# MPPT-BCR.net
KiCad netlist of a schematic drawn in Altium Designer
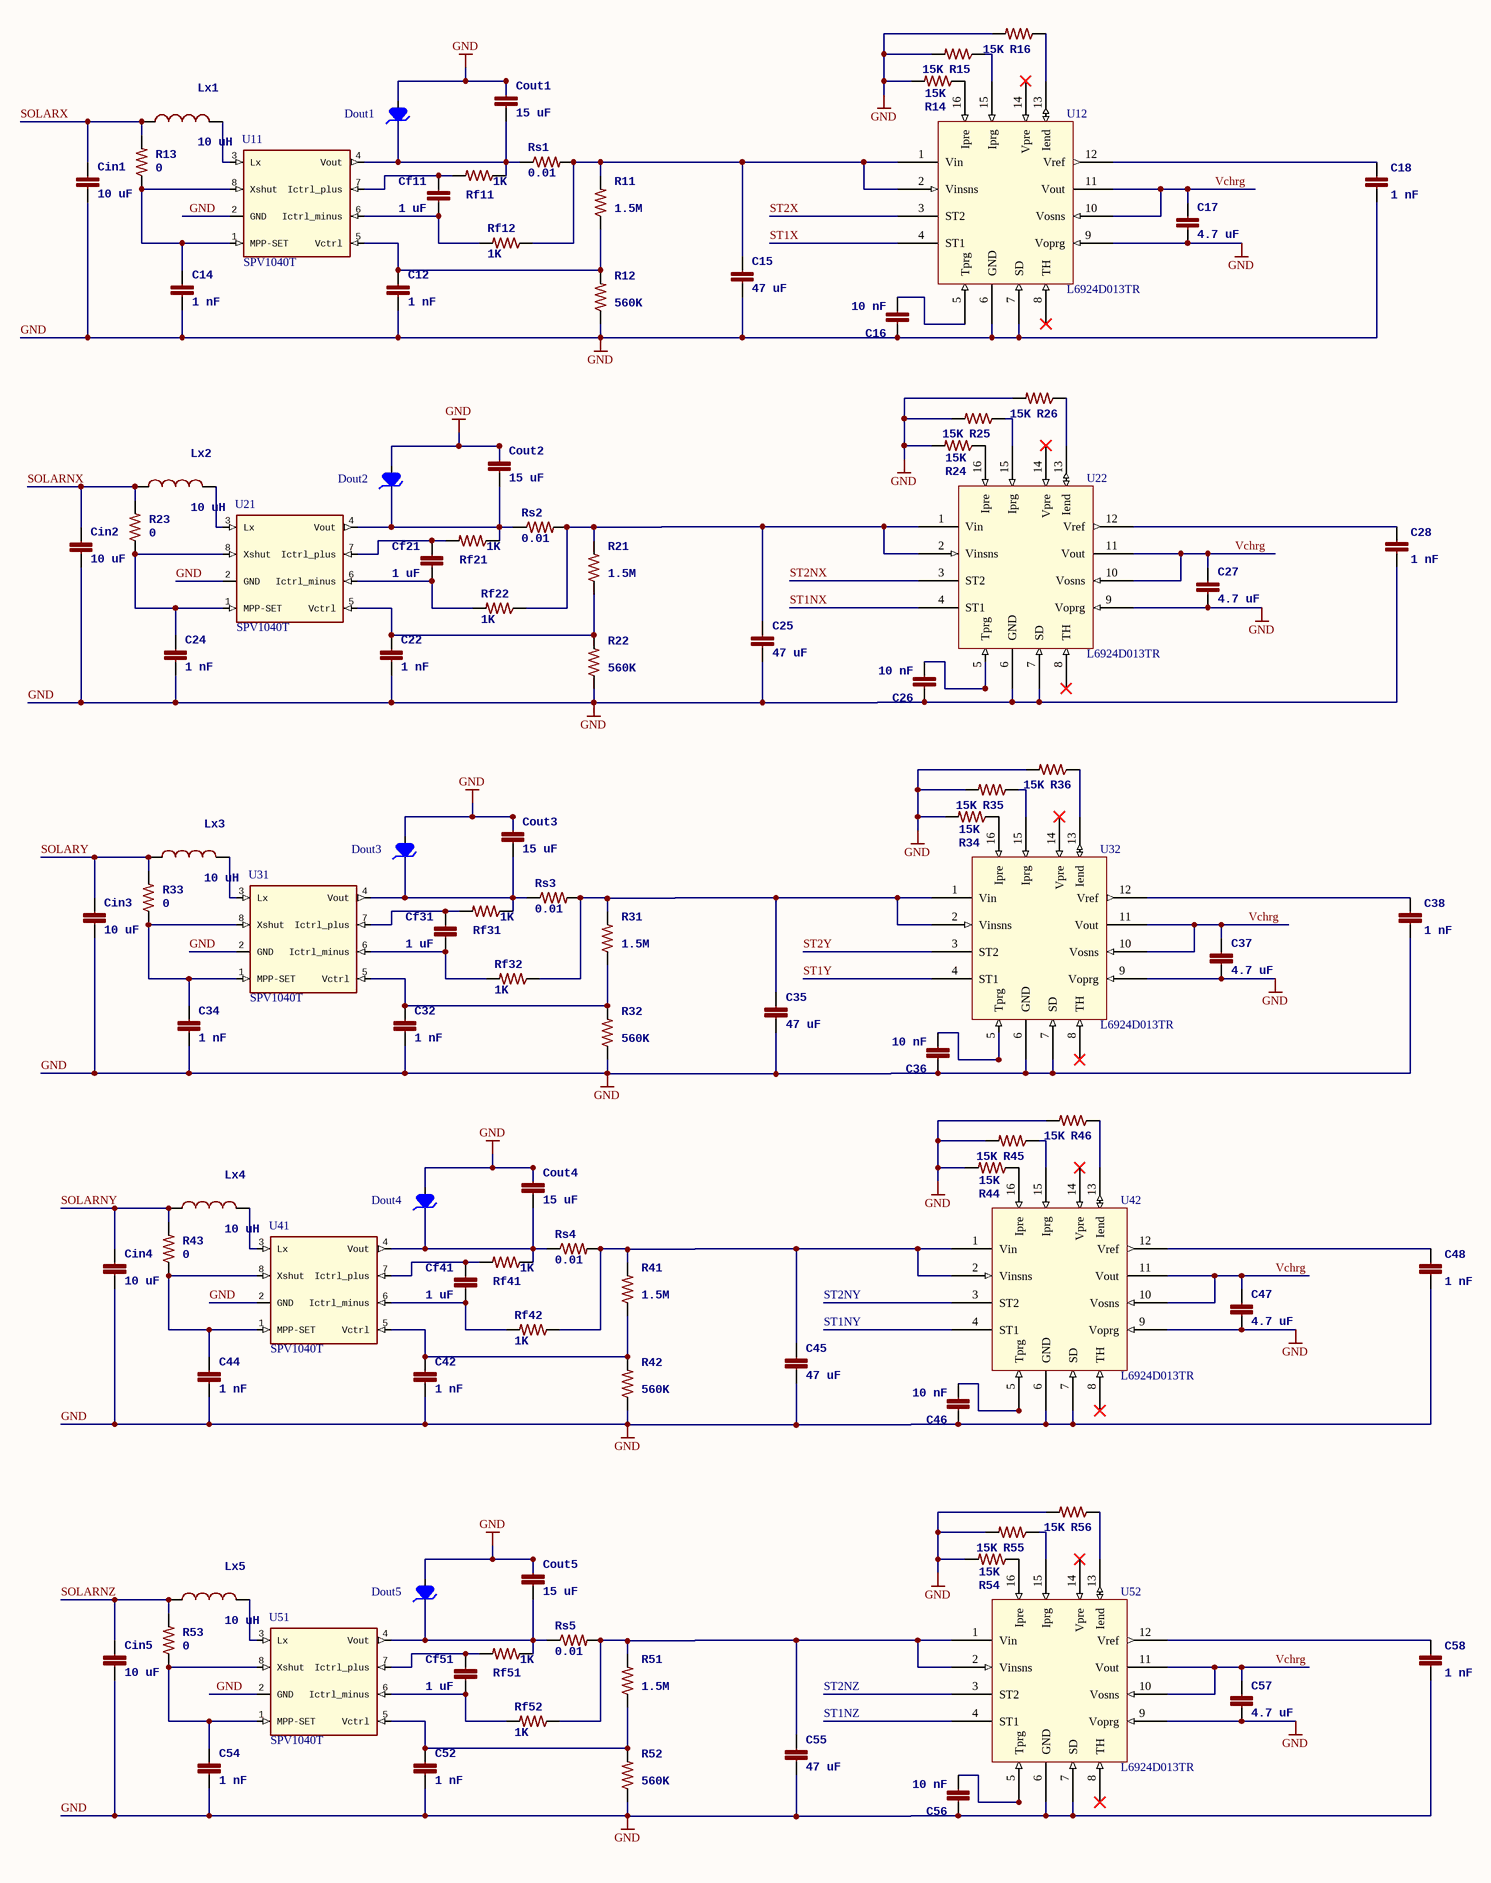
[diagram p0: MPPT-BCR.SchDoc]

(export (version "E")
  (design (tool "Eeschema 10.0.6"))
  (components
    (comp (ref "C12")
      (value "1 nF")
      (footprint "0805")
      (fields (field (name "TOLERANCE") "±10%"))
      (libsource (lib "yusend_power") (part "CAP0805_1nF"))
    )
    (comp (ref "C14")
      (value "1 nF")
      (footprint "0805")
      (fields (field (name "TOLERANCE") "±10%"))
      (libsource (lib "yusend_power") (part "CAP0805_1nF"))
    )
    (comp (ref "C15")
      (value "47 uF")
      (footprint "0805")
      (fields (field (name "TOLERANCE") "±10%"))
      (libsource (lib "yusend_power") (part "CAP0805_47000nF"))
    )
    (comp (ref "C16")
      (value "10 nF")
      (footprint "0805")
      (fields (field (name "TOLERANCE") "±10%"))
      (libsource (lib "yusend_power") (part "CAP0805_10nF"))
    )
    (comp (ref "C17")
      (value "4.7 uF")
      (footprint "0805")
      (fields (field (name "TOLERANCE") "±10%"))
      (libsource (lib "yusend_power") (part "CAP0805_4700nF"))
    )
    (comp (ref "C18")
      (value "1 nF")
      (footprint "0805")
      (fields (field (name "TOLERANCE") "±10%"))
      (libsource (lib "yusend_power") (part "CAP0805_1nF"))
    )
    (comp (ref "C22")
      (value "1 nF")
      (footprint "0805")
      (fields (field (name "TOLERANCE") "±10%"))
      (libsource (lib "yusend_power") (part "CAP0805_1nF"))
    )
    (comp (ref "C24")
      (value "1 nF")
      (footprint "0805")
      (fields (field (name "TOLERANCE") "±10%"))
      (libsource (lib "yusend_power") (part "CAP0805_1nF"))
    )
    (comp (ref "C25")
      (value "47 uF")
      (footprint "0805")
      (fields (field (name "TOLERANCE") "±10%"))
      (libsource (lib "yusend_power") (part "CAP0805_47000nF"))
    )
    (comp (ref "C26")
      (value "10 nF")
      (footprint "0805")
      (fields (field (name "TOLERANCE") "±10%"))
      (libsource (lib "yusend_power") (part "CAP0805_10nF"))
    )
    (comp (ref "C27")
      (value "4.7 uF")
      (footprint "0805")
      (fields (field (name "TOLERANCE") "±10%"))
      (libsource (lib "yusend_power") (part "CAP0805_4700nF"))
    )
    (comp (ref "C28")
      (value "1 nF")
      (footprint "0805")
      (fields (field (name "TOLERANCE") "±10%"))
      (libsource (lib "yusend_power") (part "CAP0805_1nF"))
    )
    (comp (ref "C32")
      (value "1 nF")
      (footprint "0805")
      (fields (field (name "TOLERANCE") "±10%"))
      (libsource (lib "yusend_power") (part "CAP0805_1nF"))
    )
    (comp (ref "C34")
      (value "1 nF")
      (footprint "0805")
      (fields (field (name "TOLERANCE") "±10%"))
      (libsource (lib "yusend_power") (part "CAP0805_1nF"))
    )
    (comp (ref "C35")
      (value "47 uF")
      (footprint "0805")
      (fields (field (name "TOLERANCE") "±10%"))
      (libsource (lib "yusend_power") (part "CAP0805_47000nF"))
    )
    (comp (ref "C36")
      (value "10 nF")
      (footprint "0805")
      (fields (field (name "TOLERANCE") "±10%"))
      (libsource (lib "yusend_power") (part "CAP0805_10nF"))
    )
    (comp (ref "C37")
      (value "4.7 uF")
      (footprint "0805")
      (fields (field (name "TOLERANCE") "±10%"))
      (libsource (lib "yusend_power") (part "CAP0805_4700nF"))
    )
    (comp (ref "C38")
      (value "1 nF")
      (footprint "0805")
      (fields (field (name "TOLERANCE") "±10%"))
      (libsource (lib "yusend_power") (part "CAP0805_1nF"))
    )
    (comp (ref "C42")
      (value "1 nF")
      (footprint "0805")
      (fields (field (name "TOLERANCE") "±10%"))
      (libsource (lib "yusend_power") (part "CAP0805_1nF"))
    )
    (comp (ref "C44")
      (value "1 nF")
      (footprint "0805")
      (fields (field (name "TOLERANCE") "±10%"))
      (libsource (lib "yusend_power") (part "CAP0805_1nF"))
    )
    (comp (ref "C45")
      (value "47 uF")
      (footprint "0805")
      (fields (field (name "TOLERANCE") "±10%"))
      (libsource (lib "yusend_power") (part "CAP0805_47000nF"))
    )
    (comp (ref "C46")
      (value "10 nF")
      (footprint "0805")
      (fields (field (name "TOLERANCE") "±10%"))
      (libsource (lib "yusend_power") (part "CAP0805_10nF"))
    )
    (comp (ref "C47")
      (value "4.7 uF")
      (footprint "0805")
      (fields (field (name "TOLERANCE") "±10%"))
      (libsource (lib "yusend_power") (part "CAP0805_4700nF"))
    )
    (comp (ref "C48")
      (value "1 nF")
      (footprint "0805")
      (fields (field (name "TOLERANCE") "±10%"))
      (libsource (lib "yusend_power") (part "CAP0805_1nF"))
    )
    (comp (ref "C52")
      (value "1 nF")
      (footprint "0805")
      (fields (field (name "TOLERANCE") "±10%"))
      (libsource (lib "yusend_power") (part "CAP0805_1nF"))
    )
    (comp (ref "C54")
      (value "1 nF")
      (footprint "0805")
      (fields (field (name "TOLERANCE") "±10%"))
      (libsource (lib "yusend_power") (part "CAP0805_1nF"))
    )
    (comp (ref "C55")
      (value "47 uF")
      (footprint "0805")
      (fields (field (name "TOLERANCE") "±10%"))
      (libsource (lib "yusend_power") (part "CAP0805_47000nF"))
    )
    (comp (ref "C56")
      (value "10 nF")
      (footprint "0805")
      (fields (field (name "TOLERANCE") "±10%"))
      (libsource (lib "yusend_power") (part "CAP0805_10nF"))
    )
    (comp (ref "C57")
      (value "4.7 uF")
      (footprint "0805")
      (fields (field (name "TOLERANCE") "±10%"))
      (libsource (lib "yusend_power") (part "CAP0805_4700nF"))
    )
    (comp (ref "C58")
      (value "1 nF")
      (footprint "0805")
      (fields (field (name "TOLERANCE") "±10%"))
      (libsource (lib "yusend_power") (part "CAP0805_1nF"))
    )
    (comp (ref "Cf11")
      (value "1 uF")
      (footprint "0805")
      (fields
        (field (name "MANUFACTURER") "Kemet")
        (field (name "MANUFACTURER PART NUMBER") "C0805C105K8RACTU")
        (field (name "TOLERANCE") "±10%")
      )
      (libsource (lib "yusend_power") (part "CAP0805_1uF"))
    )
    (comp (ref "Cf21")
      (value "1 uF")
      (footprint "0805")
      (fields
        (field (name "MANUFACTURER") "Kemet")
        (field (name "MANUFACTURER PART NUMBER") "C0805C105K8RACTU")
        (field (name "TOLERANCE") "±10%")
      )
      (libsource (lib "yusend_power") (part "CAP0805_1uF"))
    )
    (comp (ref "Cf31")
      (value "1 uF")
      (footprint "0805")
      (fields
        (field (name "MANUFACTURER") "Kemet")
        (field (name "MANUFACTURER PART NUMBER") "C0805C105K8RACTU")
        (field (name "TOLERANCE") "±10%")
      )
      (libsource (lib "yusend_power") (part "CAP0805_1uF"))
    )
    (comp (ref "Cf41")
      (value "1 uF")
      (footprint "0805")
      (fields
        (field (name "MANUFACTURER") "Kemet")
        (field (name "MANUFACTURER PART NUMBER") "C0805C105K8RACTU")
        (field (name "TOLERANCE") "±10%")
      )
      (libsource (lib "yusend_power") (part "CAP0805_1uF"))
    )
    (comp (ref "Cf51")
      (value "1 uF")
      (footprint "0805")
      (fields
        (field (name "MANUFACTURER") "Kemet")
        (field (name "MANUFACTURER PART NUMBER") "C0805C105K8RACTU")
        (field (name "TOLERANCE") "±10%")
      )
      (libsource (lib "yusend_power") (part "CAP0805_1uF"))
    )
    (comp (ref "Cin1")
      (value "10 uF")
      (footprint "0805")
      (fields (field (name "TOLERANCE") "±10%"))
      (libsource (lib "yusend_power") (part "CAP0805_10uF"))
    )
    (comp (ref "Cin2")
      (value "10 uF")
      (footprint "0805")
      (fields (field (name "TOLERANCE") "±10%"))
      (libsource (lib "yusend_power") (part "CAP0805_10uF"))
    )
    (comp (ref "Cin3")
      (value "10 uF")
      (footprint "0805")
      (fields (field (name "TOLERANCE") "±10%"))
      (libsource (lib "yusend_power") (part "CAP0805_10uF"))
    )
    (comp (ref "Cin4")
      (value "10 uF")
      (footprint "0805")
      (fields (field (name "TOLERANCE") "±10%"))
      (libsource (lib "yusend_power") (part "CAP0805_10uF"))
    )
    (comp (ref "Cin5")
      (value "10 uF")
      (footprint "0805")
      (fields (field (name "TOLERANCE") "±10%"))
      (libsource (lib "yusend_power") (part "CAP0805_10uF"))
    )
    (comp (ref "Cout1")
      (value "15 uF")
      (footprint "1210")
      (fields (field (name "TOLERANCE") "±10%"))
      (libsource (lib "yusend_power") (part "CAP0805_15uF"))
    )
    (comp (ref "Cout2")
      (value "15 uF")
      (footprint "1210")
      (fields (field (name "TOLERANCE") "±10%"))
      (libsource (lib "yusend_power") (part "CAP0805_15uF"))
    )
    (comp (ref "Cout3")
      (value "15 uF")
      (footprint "1210")
      (fields (field (name "TOLERANCE") "±10%"))
      (libsource (lib "yusend_power") (part "CAP0805_15uF"))
    )
    (comp (ref "Cout4")
      (value "15 uF")
      (footprint "1210")
      (fields (field (name "TOLERANCE") "±10%"))
      (libsource (lib "yusend_power") (part "CAP0805_15uF"))
    )
    (comp (ref "Cout5")
      (value "15 uF")
      (footprint "1210")
      (fields (field (name "TOLERANCE") "±10%"))
      (libsource (lib "yusend_power") (part "CAP0805_15uF"))
    )
    (comp (ref "Dout1")
      (value "Diode_Zener")
      (footprint "STmite")
      (fields (field (name "TOLERANCE") "±5%"))
      (libsource (lib "yusend_power") (part "Diode_Zener"))
    )
    (comp (ref "Dout2")
      (value "Diode_Zener")
      (footprint "STmite")
      (fields (field (name "TOLERANCE") "±5%"))
      (libsource (lib "") (part "Diode_Zener_1"))
    )
    (comp (ref "Dout3")
      (value "Diode_Zener")
      (footprint "STmite")
      (fields (field (name "TOLERANCE") "±5%"))
      (libsource (lib "yusend_power") (part "Diode_Zener"))
    )
    (comp (ref "Dout4")
      (value "Diode_Zener")
      (footprint "STmite")
      (fields (field (name "TOLERANCE") "±5%"))
      (libsource (lib "yusend_power") (part "Diode_Zener"))
    )
    (comp (ref "Dout5")
      (value "Diode_Zener")
      (footprint "STmite")
      (fields (field (name "TOLERANCE") "±5%"))
      (libsource (lib "yusend_power") (part "Diode_Zener"))
    )
    (comp (ref "Lx1")
      (value "10 uH")
      (footprint "1007")
      (libsource (lib "yusend_power") (part "INDUCTOR1007"))
    )
    (comp (ref "Lx2")
      (value "10 uH")
      (footprint "1007")
      (libsource (lib "yusend_power") (part "INDUCTOR1007"))
    )
    (comp (ref "Lx3")
      (value "10 uH")
      (footprint "1007")
      (libsource (lib "yusend_power") (part "INDUCTOR1007"))
    )
    (comp (ref "Lx4")
      (value "10 uH")
      (footprint "1007")
      (libsource (lib "yusend_power") (part "INDUCTOR1007"))
    )
    (comp (ref "Lx5")
      (value "10 uH")
      (footprint "1007")
      (libsource (lib "yusend_power") (part "INDUCTOR1007"))
    )
    (comp (ref "R11")
      (value "1.5M")
      (footprint "0805")
      (fields
        (field (name "MANUFACTURER") "TE Connectivity")
        (field (name "MANUFACTURER PART NUMBER") "1625856-2")
        (field (name "TOLERANCE") "±10%")
      )
      (libsource (lib "yusend_power") (part "RES_0805_1500K"))
    )
    (comp (ref "R12")
      (value "560K")
      (footprint "0805")
      (fields
        (field (name "MANUFACTURER") "TE Connectivity")
        (field (name "MANUFACTURER PART NUMBER") "1625856-2")
        (field (name "TOLERANCE") "±10%")
      )
      (libsource (lib "yusend_power") (part "RES_0805_560K"))
    )
    (comp (ref "R13")
      (value "0")
      (footprint "0805")
      (fields
        (field (name "MANUFACTURER") "TE Connectivity")
        (field (name "MANUFACTURER PART NUMBER") "1625856-2")
        (field (name "TOLERANCE") "±10%")
      )
      (libsource (lib "yusend_power") (part "RES_0805_0"))
    )
    (comp (ref "R14")
      (value "15K")
      (footprint "0805")
      (fields
        (field (name "MANUFACTURER") "TE Connectivity")
        (field (name "MANUFACTURER PART NUMBER") "1625856-2")
        (field (name "TOLERANCE") "±10%")
      )
      (libsource (lib "yusend_power") (part "RES_0805_15K"))
    )
    (comp (ref "R15")
      (value "15K")
      (footprint "0805")
      (fields
        (field (name "MANUFACTURER") "TE Connectivity")
        (field (name "MANUFACTURER PART NUMBER") "1625856-2")
        (field (name "TOLERANCE") "±10%")
      )
      (libsource (lib "yusend_power") (part "RES_0805_15K"))
    )
    (comp (ref "R16")
      (value "15K")
      (footprint "0805")
      (fields
        (field (name "MANUFACTURER") "TE Connectivity")
        (field (name "MANUFACTURER PART NUMBER") "1625856-2")
        (field (name "TOLERANCE") "±10%")
      )
      (libsource (lib "yusend_power") (part "RES_0805_15K"))
    )
    (comp (ref "R21")
      (value "1.5M")
      (footprint "0805")
      (fields
        (field (name "MANUFACTURER") "TE Connectivity")
        (field (name "MANUFACTURER PART NUMBER") "1625856-2")
        (field (name "TOLERANCE") "±10%")
      )
      (libsource (lib "yusend_power") (part "RES_0805_1500K"))
    )
    (comp (ref "R22")
      (value "560K")
      (footprint "0805")
      (fields
        (field (name "MANUFACTURER") "TE Connectivity")
        (field (name "MANUFACTURER PART NUMBER") "1625856-2")
        (field (name "TOLERANCE") "±10%")
      )
      (libsource (lib "yusend_power") (part "RES_0805_560K"))
    )
    (comp (ref "R23")
      (value "0")
      (footprint "0805")
      (fields
        (field (name "MANUFACTURER") "TE Connectivity")
        (field (name "MANUFACTURER PART NUMBER") "1625856-2")
        (field (name "TOLERANCE") "±10%")
      )
      (libsource (lib "yusend_power") (part "RES_0805_0"))
    )
    (comp (ref "R24")
      (value "15K")
      (footprint "0805")
      (fields
        (field (name "MANUFACTURER") "TE Connectivity")
        (field (name "MANUFACTURER PART NUMBER") "1625856-2")
        (field (name "TOLERANCE") "±10%")
      )
      (libsource (lib "yusend_power") (part "RES_0805_15K"))
    )
    (comp (ref "R25")
      (value "15K")
      (footprint "0805")
      (fields
        (field (name "MANUFACTURER") "TE Connectivity")
        (field (name "MANUFACTURER PART NUMBER") "1625856-2")
        (field (name "TOLERANCE") "±10%")
      )
      (libsource (lib "yusend_power") (part "RES_0805_15K"))
    )
    (comp (ref "R26")
      (value "15K")
      (footprint "0805")
      (fields
        (field (name "MANUFACTURER") "TE Connectivity")
        (field (name "MANUFACTURER PART NUMBER") "1625856-2")
        (field (name "TOLERANCE") "±10%")
      )
      (libsource (lib "yusend_power") (part "RES_0805_15K"))
    )
    (comp (ref "R31")
      (value "1.5M")
      (footprint "0805")
      (fields
        (field (name "MANUFACTURER") "TE Connectivity")
        (field (name "MANUFACTURER PART NUMBER") "1625856-2")
        (field (name "TOLERANCE") "±10%")
      )
      (libsource (lib "yusend_power") (part "RES_0805_1500K"))
    )
    (comp (ref "R32")
      (value "560K")
      (footprint "0805")
      (fields
        (field (name "MANUFACTURER") "TE Connectivity")
        (field (name "MANUFACTURER PART NUMBER") "1625856-2")
        (field (name "TOLERANCE") "±10%")
      )
      (libsource (lib "yusend_power") (part "RES_0805_560K"))
    )
    (comp (ref "R33")
      (value "0")
      (footprint "0805")
      (fields
        (field (name "MANUFACTURER") "TE Connectivity")
        (field (name "MANUFACTURER PART NUMBER") "1625856-2")
        (field (name "TOLERANCE") "±10%")
      )
      (libsource (lib "yusend_power") (part "RES_0805_0"))
    )
    (comp (ref "R34")
      (value "15K")
      (footprint "0805")
      (fields
        (field (name "MANUFACTURER") "TE Connectivity")
        (field (name "MANUFACTURER PART NUMBER") "1625856-2")
        (field (name "TOLERANCE") "±10%")
      )
      (libsource (lib "yusend_power") (part "RES_0805_15K"))
    )
    (comp (ref "R35")
      (value "15K")
      (footprint "0805")
      (fields
        (field (name "MANUFACTURER") "TE Connectivity")
        (field (name "MANUFACTURER PART NUMBER") "1625856-2")
        (field (name "TOLERANCE") "±10%")
      )
      (libsource (lib "yusend_power") (part "RES_0805_15K"))
    )
    (comp (ref "R36")
      (value "15K")
      (footprint "0805")
      (fields
        (field (name "MANUFACTURER") "TE Connectivity")
        (field (name "MANUFACTURER PART NUMBER") "1625856-2")
        (field (name "TOLERANCE") "±10%")
      )
      (libsource (lib "yusend_power") (part "RES_0805_15K"))
    )
    (comp (ref "R41")
      (value "1.5M")
      (footprint "0805")
      (fields
        (field (name "MANUFACTURER") "TE Connectivity")
        (field (name "MANUFACTURER PART NUMBER") "1625856-2")
        (field (name "TOLERANCE") "±10%")
      )
      (libsource (lib "yusend_power") (part "RES_0805_1500K"))
    )
    (comp (ref "R42")
      (value "560K")
      (footprint "0805")
      (fields
        (field (name "MANUFACTURER") "TE Connectivity")
        (field (name "MANUFACTURER PART NUMBER") "1625856-2")
        (field (name "TOLERANCE") "±10%")
      )
      (libsource (lib "yusend_power") (part "RES_0805_560K"))
    )
    (comp (ref "R43")
      (value "0")
      (footprint "0805")
      (fields
        (field (name "MANUFACTURER") "TE Connectivity")
        (field (name "MANUFACTURER PART NUMBER") "1625856-2")
        (field (name "TOLERANCE") "±10%")
      )
      (libsource (lib "yusend_power") (part "RES_0805_0"))
    )
    (comp (ref "R44")
      (value "15K")
      (footprint "0805")
      (fields
        (field (name "MANUFACTURER") "TE Connectivity")
        (field (name "MANUFACTURER PART NUMBER") "1625856-2")
        (field (name "TOLERANCE") "±10%")
      )
      (libsource (lib "yusend_power") (part "RES_0805_15K"))
    )
    (comp (ref "R45")
      (value "15K")
      (footprint "0805")
      (fields
        (field (name "MANUFACTURER") "TE Connectivity")
        (field (name "MANUFACTURER PART NUMBER") "1625856-2")
        (field (name "TOLERANCE") "±10%")
      )
      (libsource (lib "yusend_power") (part "RES_0805_15K"))
    )
    (comp (ref "R46")
      (value "15K")
      (footprint "0805")
      (fields
        (field (name "MANUFACTURER") "TE Connectivity")
        (field (name "MANUFACTURER PART NUMBER") "1625856-2")
        (field (name "TOLERANCE") "±10%")
      )
      (libsource (lib "yusend_power") (part "RES_0805_15K"))
    )
    (comp (ref "R51")
      (value "1.5M")
      (footprint "0805")
      (fields
        (field (name "MANUFACTURER") "TE Connectivity")
        (field (name "MANUFACTURER PART NUMBER") "1625856-2")
        (field (name "TOLERANCE") "±10%")
      )
      (libsource (lib "yusend_power") (part "RES_0805_1500K"))
    )
    (comp (ref "R52")
      (value "560K")
      (footprint "0805")
      (fields
        (field (name "MANUFACTURER") "TE Connectivity")
        (field (name "MANUFACTURER PART NUMBER") "1625856-2")
        (field (name "TOLERANCE") "±10%")
      )
      (libsource (lib "yusend_power") (part "RES_0805_560K"))
    )
    (comp (ref "R53")
      (value "0")
      (footprint "0805")
      (fields
        (field (name "MANUFACTURER") "TE Connectivity")
        (field (name "MANUFACTURER PART NUMBER") "1625856-2")
        (field (name "TOLERANCE") "±10%")
      )
      (libsource (lib "yusend_power") (part "RES_0805_0"))
    )
    (comp (ref "R54")
      (value "15K")
      (footprint "0805")
      (fields
        (field (name "MANUFACTURER") "TE Connectivity")
        (field (name "MANUFACTURER PART NUMBER") "1625856-2")
        (field (name "TOLERANCE") "±10%")
      )
      (libsource (lib "yusend_power") (part "RES_0805_15K"))
    )
    (comp (ref "R55")
      (value "15K")
      (footprint "0805")
      (fields
        (field (name "MANUFACTURER") "TE Connectivity")
        (field (name "MANUFACTURER PART NUMBER") "1625856-2")
        (field (name "TOLERANCE") "±10%")
      )
      (libsource (lib "yusend_power") (part "RES_0805_15K"))
    )
    (comp (ref "R56")
      (value "15K")
      (footprint "0805")
      (fields
        (field (name "MANUFACTURER") "TE Connectivity")
        (field (name "MANUFACTURER PART NUMBER") "1625856-2")
        (field (name "TOLERANCE") "±10%")
      )
      (libsource (lib "yusend_power") (part "RES_0805_15K"))
    )
    (comp (ref "Rf11")
      (value "1K")
      (footprint "0805")
      (fields
        (field (name "MANUFACTURER") "TE Connectivity")
        (field (name "MANUFACTURER PART NUMBER") "1625856-2")
        (field (name "TOLERANCE") "±10%")
      )
      (libsource (lib "yusend_power") (part "RES_0805_1K"))
    )
    (comp (ref "Rf12")
      (value "1K")
      (footprint "0805")
      (fields
        (field (name "MANUFACTURER") "TE Connectivity")
        (field (name "MANUFACTURER PART NUMBER") "1625856-2")
        (field (name "TOLERANCE") "±10%")
      )
      (libsource (lib "yusend_power") (part "RES_0805_1K"))
    )
    (comp (ref "Rf21")
      (value "1K")
      (footprint "0805")
      (fields
        (field (name "MANUFACTURER") "TE Connectivity")
        (field (name "MANUFACTURER PART NUMBER") "1625856-2")
        (field (name "TOLERANCE") "±10%")
      )
      (libsource (lib "yusend_power") (part "RES_0805_1K"))
    )
    (comp (ref "Rf22")
      (value "1K")
      (footprint "0805")
      (fields
        (field (name "MANUFACTURER") "TE Connectivity")
        (field (name "MANUFACTURER PART NUMBER") "1625856-2")
        (field (name "TOLERANCE") "±10%")
      )
      (libsource (lib "yusend_power") (part "RES_0805_1K"))
    )
    (comp (ref "Rf31")
      (value "1K")
      (footprint "0805")
      (fields
        (field (name "MANUFACTURER") "TE Connectivity")
        (field (name "MANUFACTURER PART NUMBER") "1625856-2")
        (field (name "TOLERANCE") "±10%")
      )
      (libsource (lib "yusend_power") (part "RES_0805_1K"))
    )
    (comp (ref "Rf32")
      (value "1K")
      (footprint "0805")
      (fields
        (field (name "MANUFACTURER") "TE Connectivity")
        (field (name "MANUFACTURER PART NUMBER") "1625856-2")
        (field (name "TOLERANCE") "±10%")
      )
      (libsource (lib "yusend_power") (part "RES_0805_1K"))
    )
    (comp (ref "Rf41")
      (value "1K")
      (footprint "0805")
      (fields
        (field (name "MANUFACTURER") "TE Connectivity")
        (field (name "MANUFACTURER PART NUMBER") "1625856-2")
        (field (name "TOLERANCE") "±10%")
      )
      (libsource (lib "yusend_power") (part "RES_0805_1K"))
    )
    (comp (ref "Rf42")
      (value "1K")
      (footprint "0805")
      (fields
        (field (name "MANUFACTURER") "TE Connectivity")
        (field (name "MANUFACTURER PART NUMBER") "1625856-2")
        (field (name "TOLERANCE") "±10%")
      )
      (libsource (lib "yusend_power") (part "RES_0805_1K"))
    )
    (comp (ref "Rf51")
      (value "1K")
      (footprint "0805")
      (fields
        (field (name "MANUFACTURER") "TE Connectivity")
        (field (name "MANUFACTURER PART NUMBER") "1625856-2")
        (field (name "TOLERANCE") "±10%")
      )
      (libsource (lib "yusend_power") (part "RES_0805_1K"))
    )
    (comp (ref "Rf52")
      (value "1K")
      (footprint "0805")
      (fields
        (field (name "MANUFACTURER") "TE Connectivity")
        (field (name "MANUFACTURER PART NUMBER") "1625856-2")
        (field (name "TOLERANCE") "±10%")
      )
      (libsource (lib "yusend_power") (part "RES_0805_1K"))
    )
    (comp (ref "Rs1")
      (value "0.01")
      (footprint "0805")
      (fields
        (field (name "MANUFACTURER") "TE Connectivity")
        (field (name "MANUFACTURER PART NUMBER") "1625856-2")
        (field (name "TOLERANCE") "±10%")
      )
      (libsource (lib "yusend_power") (part "RES_0805_01"))
    )
    (comp (ref "Rs2")
      (value "0.01")
      (footprint "0805")
      (fields
        (field (name "MANUFACTURER") "TE Connectivity")
        (field (name "MANUFACTURER PART NUMBER") "1625856-2")
        (field (name "TOLERANCE") "±10%")
      )
      (libsource (lib "yusend_power") (part "RES_0805_01"))
    )
    (comp (ref "Rs3")
      (value "0.01")
      (footprint "0805")
      (fields
        (field (name "MANUFACTURER") "TE Connectivity")
        (field (name "MANUFACTURER PART NUMBER") "1625856-2")
        (field (name "TOLERANCE") "±10%")
      )
      (libsource (lib "yusend_power") (part "RES_0805_01"))
    )
    (comp (ref "Rs4")
      (value "0.01")
      (footprint "0805")
      (fields
        (field (name "MANUFACTURER") "TE Connectivity")
        (field (name "MANUFACTURER PART NUMBER") "1625856-2")
        (field (name "TOLERANCE") "±10%")
      )
      (libsource (lib "yusend_power") (part "RES_0805_01"))
    )
    (comp (ref "Rs5")
      (value "0.01")
      (footprint "0805")
      (fields
        (field (name "MANUFACTURER") "TE Connectivity")
        (field (name "MANUFACTURER PART NUMBER") "1625856-2")
        (field (name "TOLERANCE") "±10%")
      )
      (libsource (lib "yusend_power") (part "RES_0805_01"))
    )
    (comp (ref "U11")
      (value "SPV1040")
      (footprint "TSSOP8")
      (fields
        (field (name "MANUFACTURER") "STMicroelectronics")
        (field (name "MANUFACTURER PART NUMBER") "SPV1040T")
      )
      (libsource (lib "yusend_power") (part "SPV1040"))
    )
    (comp (ref "U12")
      (value "L6924D013TR")
      (footprint "VQFN16_AP")
      (description "IC BATT CHRGR ION/POLY 16-VFQFPN")
      (fields (field (name "MANUFACTURER") "STMicroelectronics"))
      (libsource (lib "yusend_power") (part "L6924D013TR"))
    )
    (comp (ref "U21")
      (value "SPV1040")
      (footprint "TSSOP8")
      (fields
        (field (name "MANUFACTURER") "STMicroelectronics")
        (field (name "MANUFACTURER PART NUMBER") "SPV1040T")
      )
      (libsource (lib "") (part "SPV1040_1"))
    )
    (comp (ref "U22")
      (value "L6924D013TR")
      (footprint "VQFN16_AP")
      (description "IC BATT CHRGR ION/POLY 16-VFQFPN")
      (fields (field (name "MANUFACTURER") "STMicroelectronics"))
      (libsource (lib "yusend_power") (part "L6924D013TR"))
    )
    (comp (ref "U31")
      (value "SPV1040")
      (footprint "TSSOP8")
      (fields
        (field (name "MANUFACTURER") "STMicroelectronics")
        (field (name "MANUFACTURER PART NUMBER") "SPV1040T")
      )
      (libsource (lib "yusend_power") (part "SPV1040"))
    )
    (comp (ref "U32")
      (value "L6924D013TR")
      (footprint "VQFN16_AP")
      (description "IC BATT CHRGR ION/POLY 16-VFQFPN")
      (fields (field (name "MANUFACTURER") "STMicroelectronics"))
      (libsource (lib "yusend_power") (part "L6924D013TR"))
    )
    (comp (ref "U41")
      (value "SPV1040")
      (footprint "TSSOP8")
      (fields
        (field (name "MANUFACTURER") "STMicroelectronics")
        (field (name "MANUFACTURER PART NUMBER") "SPV1040T")
      )
      (libsource (lib "yusend_power") (part "SPV1040"))
    )
    (comp (ref "U42")
      (value "L6924D013TR")
      (footprint "VQFN16_AP")
      (description "IC BATT CHRGR ION/POLY 16-VFQFPN")
      (fields (field (name "MANUFACTURER") "STMicroelectronics"))
      (libsource (lib "yusend_power") (part "L6924D013TR"))
    )
    (comp (ref "U51")
      (value "SPV1040")
      (footprint "TSSOP8")
      (fields
        (field (name "MANUFACTURER") "STMicroelectronics")
        (field (name "MANUFACTURER PART NUMBER") "SPV1040T")
      )
      (libsource (lib "yusend_power") (part "SPV1040"))
    )
    (comp (ref "U52")
      (value "L6924D013TR")
      (footprint "VQFN16_AP")
      (description "IC BATT CHRGR ION/POLY 16-VFQFPN")
      (fields (field (name "MANUFACTURER") "STMicroelectronics"))
      (libsource (lib "yusend_power") (part "L6924D013TR"))
    )
  )
  (nets
    (net (code "1") (name "/SOLARNX") (class "Default")
      (node (ref "Cin2") (pin "1") (pinfunction "1_1") (pintype "passive"))
      (node (ref "Lx2") (pin "1") (pinfunction "1_1") (pintype "passive"))
      (node (ref "R23") (pin "2") (pinfunction "2_2") (pintype "passive"))
    )
    (net (code "2") (name "/SOLARNY") (class "Default")
      (node (ref "Cin4") (pin "1") (pinfunction "1_1") (pintype "passive"))
      (node (ref "Lx4") (pin "1") (pinfunction "1_1") (pintype "passive"))
      (node (ref "R43") (pin "2") (pinfunction "2_2") (pintype "passive"))
    )
    (net (code "3") (name "/SOLARNZ") (class "Default")
      (node (ref "Cin5") (pin "1") (pinfunction "1_1") (pintype "passive"))
      (node (ref "Lx5") (pin "1") (pinfunction "1_1") (pintype "passive"))
      (node (ref "R53") (pin "2") (pinfunction "2_2") (pintype "passive"))
    )
    (net (code "4") (name "/SOLARX") (class "Default")
      (node (ref "Cin1") (pin "1") (pinfunction "1_1") (pintype "passive"))
      (node (ref "Lx1") (pin "1") (pinfunction "1_1") (pintype "passive"))
      (node (ref "R13") (pin "2") (pinfunction "2_2") (pintype "passive"))
    )
    (net (code "5") (name "/SOLARY") (class "Default")
      (node (ref "Cin3") (pin "1") (pinfunction "1_1") (pintype "passive"))
      (node (ref "Lx3") (pin "1") (pinfunction "1_1") (pintype "passive"))
      (node (ref "R33") (pin "2") (pinfunction "2_2") (pintype "passive"))
    )
    (net (code "6") (name "/ST1NX") (class "Default")
      (node (ref "U22") (pin "4") (pinfunction "ST1_4") (pintype "open_collector"))
    )
    (net (code "7") (name "/ST1X") (class "Default")
      (node (ref "U12") (pin "4") (pinfunction "ST1_4") (pintype "open_collector"))
    )
    (net (code "8") (name "/ST1Y") (class "Default")
      (node (ref "U32") (pin "4") (pinfunction "ST1_4") (pintype "open_collector"))
    )
    (net (code "9") (name "/ST2NX") (class "Default")
      (node (ref "U22") (pin "3") (pinfunction "ST2_3") (pintype "open_collector"))
    )
    (net (code "10") (name "/ST2X") (class "Default")
      (node (ref "U12") (pin "3") (pinfunction "ST2_3") (pintype "open_collector"))
    )
    (net (code "11") (name "/ST2Y") (class "Default")
      (node (ref "U32") (pin "3") (pinfunction "ST2_3") (pintype "open_collector"))
    )
    (net (code "12") (name "/Vchrg") (class "Default")
      (node (ref "C17") (pin "1") (pinfunction "1_1") (pintype "passive"))
      (node (ref "C27") (pin "1") (pinfunction "1_1") (pintype "passive"))
      (node (ref "C37") (pin "1") (pinfunction "1_1") (pintype "passive"))
      (node (ref "C47") (pin "1") (pinfunction "1_1") (pintype "passive"))
      (node (ref "C57") (pin "1") (pinfunction "1_1") (pintype "passive"))
      (node (ref "U12") (pin "10") (pinfunction "Vosns_10") (pintype "input"))
      (node (ref "U12") (pin "11") (pinfunction "Vout_11") (pintype "power_in"))
      (node (ref "U22") (pin "10") (pinfunction "Vosns_10") (pintype "input"))
      (node (ref "U22") (pin "11") (pinfunction "Vout_11") (pintype "power_in"))
      (node (ref "U32") (pin "10") (pinfunction "Vosns_10") (pintype "input"))
      (node (ref "U32") (pin "11") (pinfunction "Vout_11") (pintype "power_in"))
      (node (ref "U42") (pin "10") (pinfunction "Vosns_10") (pintype "input"))
      (node (ref "U42") (pin "11") (pinfunction "Vout_11") (pintype "power_in"))
      (node (ref "U52") (pin "10") (pinfunction "Vosns_10") (pintype "input"))
      (node (ref "U52") (pin "11") (pinfunction "Vout_11") (pintype "power_in"))
    )
    (net (code "13") (name "GND") (class "Default")
      (node (ref "C12") (pin "2") (pinfunction "2_2") (pintype "passive"))
      (node (ref "C14") (pin "2") (pinfunction "2_2") (pintype "passive"))
      (node (ref "C15") (pin "2") (pinfunction "2_2") (pintype "passive"))
      (node (ref "C16") (pin "1") (pinfunction "1_1") (pintype "passive"))
      (node (ref "C17") (pin "2") (pinfunction "2_2") (pintype "passive"))
      (node (ref "C18") (pin "2") (pinfunction "2_2") (pintype "passive"))
      (node (ref "C22") (pin "2") (pinfunction "2_2") (pintype "passive"))
      (node (ref "C24") (pin "2") (pinfunction "2_2") (pintype "passive"))
      (node (ref "C25") (pin "2") (pinfunction "2_2") (pintype "passive"))
      (node (ref "C26") (pin "1") (pinfunction "1_1") (pintype "passive"))
      (node (ref "C27") (pin "2") (pinfunction "2_2") (pintype "passive"))
      (node (ref "C28") (pin "2") (pinfunction "2_2") (pintype "passive"))
      (node (ref "C32") (pin "2") (pinfunction "2_2") (pintype "passive"))
      (node (ref "C34") (pin "2") (pinfunction "2_2") (pintype "passive"))
      (node (ref "C35") (pin "2") (pinfunction "2_2") (pintype "passive"))
      (node (ref "C36") (pin "1") (pinfunction "1_1") (pintype "passive"))
      (node (ref "C37") (pin "2") (pinfunction "2_2") (pintype "passive"))
      (node (ref "C38") (pin "2") (pinfunction "2_2") (pintype "passive"))
      (node (ref "C42") (pin "2") (pinfunction "2_2") (pintype "passive"))
      (node (ref "C44") (pin "2") (pinfunction "2_2") (pintype "passive"))
      (node (ref "C45") (pin "2") (pinfunction "2_2") (pintype "passive"))
      (node (ref "C46") (pin "1") (pinfunction "1_1") (pintype "passive"))
      (node (ref "C47") (pin "2") (pinfunction "2_2") (pintype "passive"))
      (node (ref "C48") (pin "2") (pinfunction "2_2") (pintype "passive"))
      (node (ref "C52") (pin "2") (pinfunction "2_2") (pintype "passive"))
      (node (ref "C54") (pin "2") (pinfunction "2_2") (pintype "passive"))
      (node (ref "C55") (pin "2") (pinfunction "2_2") (pintype "passive"))
      (node (ref "C56") (pin "1") (pinfunction "1_1") (pintype "passive"))
      (node (ref "C57") (pin "2") (pinfunction "2_2") (pintype "passive"))
      (node (ref "C58") (pin "2") (pinfunction "2_2") (pintype "passive"))
      (node (ref "Cin1") (pin "2") (pinfunction "2_2") (pintype "passive"))
      (node (ref "Cin2") (pin "2") (pinfunction "2_2") (pintype "passive"))
      (node (ref "Cin3") (pin "2") (pinfunction "2_2") (pintype "passive"))
      (node (ref "Cin4") (pin "2") (pinfunction "2_2") (pintype "passive"))
      (node (ref "Cin5") (pin "2") (pinfunction "2_2") (pintype "passive"))
      (node (ref "Cout1") (pin "1") (pinfunction "1_1") (pintype "passive"))
      (node (ref "Cout2") (pin "1") (pinfunction "1_1") (pintype "passive"))
      (node (ref "Cout3") (pin "1") (pinfunction "1_1") (pintype "passive"))
      (node (ref "Cout4") (pin "1") (pinfunction "1_1") (pintype "passive"))
      (node (ref "Cout5") (pin "1") (pinfunction "1_1") (pintype "passive"))
      (node (ref "Dout1") (pin "2") (pinfunction "2_2") (pintype "passive"))
      (node (ref "Dout2") (pin "2") (pinfunction "2_2") (pintype "passive"))
      (node (ref "Dout3") (pin "2") (pinfunction "2_2") (pintype "passive"))
      (node (ref "Dout4") (pin "2") (pinfunction "2_2") (pintype "passive"))
      (node (ref "Dout5") (pin "2") (pinfunction "2_2") (pintype "passive"))
      (node (ref "R12") (pin "1") (pinfunction "1_1") (pintype "passive"))
      (node (ref "R14") (pin "2") (pinfunction "2_2") (pintype "passive"))
      (node (ref "R15") (pin "2") (pinfunction "2_2") (pintype "passive"))
      (node (ref "R16") (pin "2") (pinfunction "2_2") (pintype "passive"))
      (node (ref "R22") (pin "1") (pinfunction "1_1") (pintype "passive"))
      (node (ref "R24") (pin "2") (pinfunction "2_2") (pintype "passive"))
      (node (ref "R25") (pin "2") (pinfunction "2_2") (pintype "passive"))
      (node (ref "R26") (pin "2") (pinfunction "2_2") (pintype "passive"))
      (node (ref "R32") (pin "1") (pinfunction "1_1") (pintype "passive"))
      (node (ref "R34") (pin "2") (pinfunction "2_2") (pintype "passive"))
      (node (ref "R35") (pin "2") (pinfunction "2_2") (pintype "passive"))
      (node (ref "R36") (pin "2") (pinfunction "2_2") (pintype "passive"))
      (node (ref "R42") (pin "1") (pinfunction "1_1") (pintype "passive"))
      (node (ref "R44") (pin "2") (pinfunction "2_2") (pintype "passive"))
      (node (ref "R45") (pin "2") (pinfunction "2_2") (pintype "passive"))
      (node (ref "R46") (pin "2") (pinfunction "2_2") (pintype "passive"))
      (node (ref "R52") (pin "1") (pinfunction "1_1") (pintype "passive"))
      (node (ref "R54") (pin "2") (pinfunction "2_2") (pintype "passive"))
      (node (ref "R55") (pin "2") (pinfunction "2_2") (pintype "passive"))
      (node (ref "R56") (pin "2") (pinfunction "2_2") (pintype "passive"))
      (node (ref "U11") (pin "2") (pinfunction "GND_2") (pintype "passive"))
      (node (ref "U12") (pin "6") (pinfunction "GND_6") (pintype "power_in"))
      (node (ref "U12") (pin "7") (pinfunction "SD_7") (pintype "input"))
      (node (ref "U12") (pin "9") (pinfunction "Voprg_9") (pintype "input"))
      (node (ref "U21") (pin "2") (pinfunction "GND_2") (pintype "passive"))
      (node (ref "U22") (pin "6") (pinfunction "GND_6") (pintype "power_in"))
      (node (ref "U22") (pin "7") (pinfunction "SD_7") (pintype "input"))
      (node (ref "U22") (pin "9") (pinfunction "Voprg_9") (pintype "input"))
      (node (ref "U31") (pin "2") (pinfunction "GND_2") (pintype "passive"))
      (node (ref "U32") (pin "6") (pinfunction "GND_6") (pintype "power_in"))
      (node (ref "U32") (pin "7") (pinfunction "SD_7") (pintype "input"))
      (node (ref "U32") (pin "9") (pinfunction "Voprg_9") (pintype "input"))
      (node (ref "U41") (pin "2") (pinfunction "GND_2") (pintype "passive"))
      (node (ref "U42") (pin "6") (pinfunction "GND_6") (pintype "power_in"))
      (node (ref "U42") (pin "7") (pinfunction "SD_7") (pintype "input"))
      (node (ref "U42") (pin "9") (pinfunction "Voprg_9") (pintype "input"))
      (node (ref "U51") (pin "2") (pinfunction "GND_2") (pintype "passive"))
      (node (ref "U52") (pin "6") (pinfunction "GND_6") (pintype "power_in"))
      (node (ref "U52") (pin "7") (pinfunction "SD_7") (pintype "input"))
      (node (ref "U52") (pin "9") (pinfunction "Voprg_9") (pintype "input"))
    )
    (net (code "14") (name "Net-(U11-Ictrl_minus)") (class "Default")
      (node (ref "Cf11") (pin "2") (pinfunction "2_2") (pintype "passive"))
      (node (ref "Rf12") (pin "2") (pinfunction "2_2") (pintype "passive"))
      (node (ref "U11") (pin "6") (pinfunction "Ictrl_minus_6") (pintype "input"))
    )
    (net (code "15") (name "Net-(U11-Ictrl_plus)") (class "Default")
      (node (ref "Cf11") (pin "1") (pinfunction "1_1") (pintype "passive"))
      (node (ref "Rf11") (pin "2") (pinfunction "2_2") (pintype "passive"))
      (node (ref "U11") (pin "7") (pinfunction "Ictrl_plus_7") (pintype "input"))
    )
    (net (code "16") (name "Net-(U11-Lx)") (class "Default")
      (node (ref "Lx1") (pin "2") (pinfunction "2_2") (pintype "passive"))
      (node (ref "U11") (pin "3") (pinfunction "Lx_3") (pintype "input"))
    )
    (net (code "17") (name "Net-(U11-MPP-SET)") (class "Default")
      (node (ref "C14") (pin "1") (pinfunction "1_1") (pintype "passive"))
      (node (ref "R13") (pin "1") (pinfunction "1_1") (pintype "passive"))
      (node (ref "U11") (pin "1") (pinfunction "MPP-SET_1") (pintype "input"))
      (node (ref "U11") (pin "8") (pinfunction "Xshut_8") (pintype "input"))
    )
    (net (code "18") (name "Net-(U11-Vctrl)") (class "Default")
      (node (ref "C12") (pin "1") (pinfunction "1_1") (pintype "passive"))
      (node (ref "R11") (pin "1") (pinfunction "1_1") (pintype "passive"))
      (node (ref "R12") (pin "2") (pinfunction "2_2") (pintype "passive"))
      (node (ref "U11") (pin "5") (pinfunction "Vctrl_5") (pintype "input"))
    )
    (net (code "19") (name "Net-(U11-Vout)") (class "Default")
      (node (ref "Cout1") (pin "2") (pinfunction "2_2") (pintype "passive"))
      (node (ref "Dout1") (pin "1") (pinfunction "1_1") (pintype "passive"))
      (node (ref "Rf11") (pin "1") (pinfunction "1_1") (pintype "passive"))
      (node (ref "Rs1") (pin "1") (pinfunction "1_1") (pintype "passive"))
      (node (ref "U11") (pin "4") (pinfunction "Vout_4") (pintype "output"))
    )
    (net (code "20") (name "Net-(U12-Iend)") (class "Default")
      (node (ref "R16") (pin "1") (pinfunction "1_1") (pintype "passive"))
      (node (ref "U12") (pin "13") (pinfunction "Iend_13") (pintype "bidirectional"))
    )
    (net (code "21") (name "Net-(U12-Ipre)") (class "Default")
      (node (ref "R14") (pin "1") (pinfunction "1_1") (pintype "passive"))
      (node (ref "U12") (pin "16") (pinfunction "Ipre_16") (pintype "input"))
    )
    (net (code "22") (name "Net-(U12-Iprg)") (class "Default")
      (node (ref "R15") (pin "1") (pinfunction "1_1") (pintype "passive"))
      (node (ref "U12") (pin "15") (pinfunction "Iprg_15") (pintype "input"))
    )
    (net (code "23") (name "Net-(U12-Tprg)") (class "Default")
      (node (ref "C16") (pin "2") (pinfunction "2_2") (pintype "passive"))
      (node (ref "U12") (pin "5") (pinfunction "Tprg_5") (pintype "input"))
    )
    (net (code "24") (name "Net-(U12-Vin)") (class "Default")
      (node (ref "C15") (pin "1") (pinfunction "1_1") (pintype "passive"))
      (node (ref "R11") (pin "2") (pinfunction "2_2") (pintype "passive"))
      (node (ref "Rf12") (pin "1") (pinfunction "1_1") (pintype "passive"))
      (node (ref "Rs1") (pin "2") (pinfunction "2_2") (pintype "passive"))
      (node (ref "U12") (pin "1") (pinfunction "Vin_1") (pintype "power_in"))
      (node (ref "U12") (pin "2") (pinfunction "Vinsns_2") (pintype "input"))
    )
    (net (code "25") (name "Net-(U12-Vref)") (class "Default")
      (node (ref "C18") (pin "1") (pinfunction "1_1") (pintype "passive"))
      (node (ref "U12") (pin "12") (pinfunction "Vref_12") (pintype "output"))
    )
    (net (code "26") (name "Net-(U21-Ictrl_minus)") (class "Default")
      (node (ref "Cf21") (pin "2") (pinfunction "2_2") (pintype "passive"))
      (node (ref "Rf22") (pin "2") (pinfunction "2_2") (pintype "passive"))
      (node (ref "U21") (pin "6") (pinfunction "Ictrl_minus_6") (pintype "input"))
    )
    (net (code "27") (name "Net-(U21-Ictrl_plus)") (class "Default")
      (node (ref "Cf21") (pin "1") (pinfunction "1_1") (pintype "passive"))
      (node (ref "Rf21") (pin "2") (pinfunction "2_2") (pintype "passive"))
      (node (ref "U21") (pin "7") (pinfunction "Ictrl_plus_7") (pintype "input"))
    )
    (net (code "28") (name "Net-(U21-Lx)") (class "Default")
      (node (ref "Lx2") (pin "2") (pinfunction "2_2") (pintype "passive"))
      (node (ref "U21") (pin "3") (pinfunction "Lx_3") (pintype "input"))
    )
    (net (code "29") (name "Net-(U21-MPP-SET)") (class "Default")
      (node (ref "C24") (pin "1") (pinfunction "1_1") (pintype "passive"))
      (node (ref "R23") (pin "1") (pinfunction "1_1") (pintype "passive"))
      (node (ref "U21") (pin "1") (pinfunction "MPP-SET_1") (pintype "input"))
      (node (ref "U21") (pin "8") (pinfunction "Xshut_8") (pintype "input"))
    )
    (net (code "30") (name "Net-(U21-Vctrl)") (class "Default")
      (node (ref "C22") (pin "1") (pinfunction "1_1") (pintype "passive"))
      (node (ref "R21") (pin "1") (pinfunction "1_1") (pintype "passive"))
      (node (ref "R22") (pin "2") (pinfunction "2_2") (pintype "passive"))
      (node (ref "U21") (pin "5") (pinfunction "Vctrl_5") (pintype "input"))
    )
    (net (code "31") (name "Net-(U21-Vout)") (class "Default")
      (node (ref "Cout2") (pin "2") (pinfunction "2_2") (pintype "passive"))
      (node (ref "Dout2") (pin "1") (pinfunction "1_1") (pintype "passive"))
      (node (ref "Rf21") (pin "1") (pinfunction "1_1") (pintype "passive"))
      (node (ref "Rs2") (pin "1") (pinfunction "1_1") (pintype "passive"))
      (node (ref "U21") (pin "4") (pinfunction "Vout_4") (pintype "output"))
    )
    (net (code "32") (name "Net-(U22-Iend)") (class "Default")
      (node (ref "R26") (pin "1") (pinfunction "1_1") (pintype "passive"))
      (node (ref "U22") (pin "13") (pinfunction "Iend_13") (pintype "bidirectional"))
    )
    (net (code "33") (name "Net-(U22-Ipre)") (class "Default")
      (node (ref "R24") (pin "1") (pinfunction "1_1") (pintype "passive"))
      (node (ref "U22") (pin "16") (pinfunction "Ipre_16") (pintype "input"))
    )
    (net (code "34") (name "Net-(U22-Iprg)") (class "Default")
      (node (ref "R25") (pin "1") (pinfunction "1_1") (pintype "passive"))
      (node (ref "U22") (pin "15") (pinfunction "Iprg_15") (pintype "input"))
    )
    (net (code "35") (name "Net-(U22-Tprg)") (class "Default")
      (node (ref "C26") (pin "2") (pinfunction "2_2") (pintype "passive"))
      (node (ref "U22") (pin "5") (pinfunction "Tprg_5") (pintype "input"))
    )
    (net (code "36") (name "Net-(U22-Vin)") (class "Default")
      (node (ref "C25") (pin "1") (pinfunction "1_1") (pintype "passive"))
      (node (ref "R21") (pin "2") (pinfunction "2_2") (pintype "passive"))
      (node (ref "Rf22") (pin "1") (pinfunction "1_1") (pintype "passive"))
      (node (ref "Rs2") (pin "2") (pinfunction "2_2") (pintype "passive"))
      (node (ref "U22") (pin "1") (pinfunction "Vin_1") (pintype "power_in"))
      (node (ref "U22") (pin "2") (pinfunction "Vinsns_2") (pintype "input"))
    )
    (net (code "37") (name "Net-(U22-Vref)") (class "Default")
      (node (ref "C28") (pin "1") (pinfunction "1_1") (pintype "passive"))
      (node (ref "U22") (pin "12") (pinfunction "Vref_12") (pintype "output"))
    )
    (net (code "38") (name "Net-(U31-Ictrl_minus)") (class "Default")
      (node (ref "Cf31") (pin "2") (pinfunction "2_2") (pintype "passive"))
      (node (ref "Rf32") (pin "2") (pinfunction "2_2") (pintype "passive"))
      (node (ref "U31") (pin "6") (pinfunction "Ictrl_minus_6") (pintype "input"))
    )
    (net (code "39") (name "Net-(U31-Ictrl_plus)") (class "Default")
      (node (ref "Cf31") (pin "1") (pinfunction "1_1") (pintype "passive"))
      (node (ref "Rf31") (pin "2") (pinfunction "2_2") (pintype "passive"))
      (node (ref "U31") (pin "7") (pinfunction "Ictrl_plus_7") (pintype "input"))
    )
    (net (code "40") (name "Net-(U31-Lx)") (class "Default")
      (node (ref "Lx3") (pin "2") (pinfunction "2_2") (pintype "passive"))
      (node (ref "U31") (pin "3") (pinfunction "Lx_3") (pintype "input"))
    )
    (net (code "41") (name "Net-(U31-MPP-SET)") (class "Default")
      (node (ref "C34") (pin "1") (pinfunction "1_1") (pintype "passive"))
      (node (ref "R33") (pin "1") (pinfunction "1_1") (pintype "passive"))
      (node (ref "U31") (pin "1") (pinfunction "MPP-SET_1") (pintype "input"))
      (node (ref "U31") (pin "8") (pinfunction "Xshut_8") (pintype "input"))
    )
    (net (code "42") (name "Net-(U31-Vctrl)") (class "Default")
      (node (ref "C32") (pin "1") (pinfunction "1_1") (pintype "passive"))
      (node (ref "R31") (pin "1") (pinfunction "1_1") (pintype "passive"))
      (node (ref "R32") (pin "2") (pinfunction "2_2") (pintype "passive"))
      (node (ref "U31") (pin "5") (pinfunction "Vctrl_5") (pintype "input"))
    )
    (net (code "43") (name "Net-(U31-Vout)") (class "Default")
      (node (ref "Cout3") (pin "2") (pinfunction "2_2") (pintype "passive"))
      (node (ref "Dout3") (pin "1") (pinfunction "1_1") (pintype "passive"))
      (node (ref "Rf31") (pin "1") (pinfunction "1_1") (pintype "passive"))
      (node (ref "Rs3") (pin "1") (pinfunction "1_1") (pintype "passive"))
      (node (ref "U31") (pin "4") (pinfunction "Vout_4") (pintype "output"))
    )
    (net (code "44") (name "Net-(U32-Iend)") (class "Default")
      (node (ref "R36") (pin "1") (pinfunction "1_1") (pintype "passive"))
      (node (ref "U32") (pin "13") (pinfunction "Iend_13") (pintype "bidirectional"))
    )
    (net (code "45") (name "Net-(U32-Ipre)") (class "Default")
      (node (ref "R34") (pin "1") (pinfunction "1_1") (pintype "passive"))
      (node (ref "U32") (pin "16") (pinfunction "Ipre_16") (pintype "input"))
    )
    (net (code "46") (name "Net-(U32-Iprg)") (class "Default")
      (node (ref "R35") (pin "1") (pinfunction "1_1") (pintype "passive"))
      (node (ref "U32") (pin "15") (pinfunction "Iprg_15") (pintype "input"))
    )
    (net (code "47") (name "Net-(U32-Tprg)") (class "Default")
      (node (ref "C36") (pin "2") (pinfunction "2_2") (pintype "passive"))
      (node (ref "U32") (pin "5") (pinfunction "Tprg_5") (pintype "input"))
    )
    (net (code "48") (name "Net-(U32-Vin)") (class "Default")
      (node (ref "C35") (pin "1") (pinfunction "1_1") (pintype "passive"))
      (node (ref "R31") (pin "2") (pinfunction "2_2") (pintype "passive"))
      (node (ref "Rf32") (pin "1") (pinfunction "1_1") (pintype "passive"))
      (node (ref "Rs3") (pin "2") (pinfunction "2_2") (pintype "passive"))
      (node (ref "U32") (pin "1") (pinfunction "Vin_1") (pintype "power_in"))
      (node (ref "U32") (pin "2") (pinfunction "Vinsns_2") (pintype "input"))
    )
    (net (code "49") (name "Net-(U32-Vref)") (class "Default")
      (node (ref "C38") (pin "1") (pinfunction "1_1") (pintype "passive"))
      (node (ref "U32") (pin "12") (pinfunction "Vref_12") (pintype "output"))
    )
    (net (code "50") (name "Net-(U41-Ictrl_minus)") (class "Default")
      (node (ref "Cf41") (pin "2") (pinfunction "2_2") (pintype "passive"))
      (node (ref "Rf42") (pin "2") (pinfunction "2_2") (pintype "passive"))
      (node (ref "U41") (pin "6") (pinfunction "Ictrl_minus_6") (pintype "input"))
    )
    (net (code "51") (name "Net-(U41-Ictrl_plus)") (class "Default")
      (node (ref "Cf41") (pin "1") (pinfunction "1_1") (pintype "passive"))
      (node (ref "Rf41") (pin "2") (pinfunction "2_2") (pintype "passive"))
      (node (ref "U41") (pin "7") (pinfunction "Ictrl_plus_7") (pintype "input"))
    )
    (net (code "52") (name "Net-(U41-Lx)") (class "Default")
      (node (ref "Lx4") (pin "2") (pinfunction "2_2") (pintype "passive"))
      (node (ref "U41") (pin "3") (pinfunction "Lx_3") (pintype "input"))
    )
    (net (code "53") (name "Net-(U41-MPP-SET)") (class "Default")
      (node (ref "C44") (pin "1") (pinfunction "1_1") (pintype "passive"))
      (node (ref "R43") (pin "1") (pinfunction "1_1") (pintype "passive"))
      (node (ref "U41") (pin "1") (pinfunction "MPP-SET_1") (pintype "input"))
      (node (ref "U41") (pin "8") (pinfunction "Xshut_8") (pintype "input"))
    )
    (net (code "54") (name "Net-(U41-Vctrl)") (class "Default")
      (node (ref "C42") (pin "1") (pinfunction "1_1") (pintype "passive"))
      (node (ref "R41") (pin "1") (pinfunction "1_1") (pintype "passive"))
      (node (ref "R42") (pin "2") (pinfunction "2_2") (pintype "passive"))
      (node (ref "U41") (pin "5") (pinfunction "Vctrl_5") (pintype "input"))
    )
    (net (code "55") (name "Net-(U41-Vout)") (class "Default")
      (node (ref "Cout4") (pin "2") (pinfunction "2_2") (pintype "passive"))
      (node (ref "Dout4") (pin "1") (pinfunction "1_1") (pintype "passive"))
      (node (ref "Rf41") (pin "1") (pinfunction "1_1") (pintype "passive"))
      (node (ref "Rs4") (pin "1") (pinfunction "1_1") (pintype "passive"))
      (node (ref "U41") (pin "4") (pinfunction "Vout_4") (pintype "output"))
    )
    (net (code "56") (name "Net-(U42-Iend)") (class "Default")
      (node (ref "R46") (pin "1") (pinfunction "1_1") (pintype "passive"))
      (node (ref "U42") (pin "13") (pinfunction "Iend_13") (pintype "bidirectional"))
    )
    (net (code "57") (name "Net-(U42-Ipre)") (class "Default")
      (node (ref "R44") (pin "1") (pinfunction "1_1") (pintype "passive"))
      (node (ref "U42") (pin "16") (pinfunction "Ipre_16") (pintype "input"))
    )
    (net (code "58") (name "Net-(U42-Iprg)") (class "Default")
      (node (ref "R45") (pin "1") (pinfunction "1_1") (pintype "passive"))
      (node (ref "U42") (pin "15") (pinfunction "Iprg_15") (pintype "input"))
    )
    (net (code "59") (name "Net-(U42-Tprg)") (class "Default")
      (node (ref "C46") (pin "2") (pinfunction "2_2") (pintype "passive"))
      (node (ref "U42") (pin "5") (pinfunction "Tprg_5") (pintype "input"))
    )
    (net (code "60") (name "Net-(U42-Vin)") (class "Default")
      (node (ref "C45") (pin "1") (pinfunction "1_1") (pintype "passive"))
      (node (ref "R41") (pin "2") (pinfunction "2_2") (pintype "passive"))
      (node (ref "Rf42") (pin "1") (pinfunction "1_1") (pintype "passive"))
      (node (ref "Rs4") (pin "2") (pinfunction "2_2") (pintype "passive"))
      (node (ref "U42") (pin "1") (pinfunction "Vin_1") (pintype "power_in"))
      (node (ref "U42") (pin "2") (pinfunction "Vinsns_2") (pintype "input"))
    )
    (net (code "61") (name "Net-(U42-Vref)") (class "Default")
      (node (ref "C48") (pin "1") (pinfunction "1_1") (pintype "passive"))
      (node (ref "U42") (pin "12") (pinfunction "Vref_12") (pintype "output"))
    )
    (net (code "62") (name "Net-(U51-Ictrl_minus)") (class "Default")
      (node (ref "Cf51") (pin "2") (pinfunction "2_2") (pintype "passive"))
      (node (ref "Rf52") (pin "2") (pinfunction "2_2") (pintype "passive"))
      (node (ref "U51") (pin "6") (pinfunction "Ictrl_minus_6") (pintype "input"))
    )
    (net (code "63") (name "Net-(U51-Ictrl_plus)") (class "Default")
      (node (ref "Cf51") (pin "1") (pinfunction "1_1") (pintype "passive"))
      (node (ref "Rf51") (pin "2") (pinfunction "2_2") (pintype "passive"))
      (node (ref "U51") (pin "7") (pinfunction "Ictrl_plus_7") (pintype "input"))
    )
    (net (code "64") (name "Net-(U51-Lx)") (class "Default")
      (node (ref "Lx5") (pin "2") (pinfunction "2_2") (pintype "passive"))
      (node (ref "U51") (pin "3") (pinfunction "Lx_3") (pintype "input"))
    )
    (net (code "65") (name "Net-(U51-MPP-SET)") (class "Default")
      (node (ref "C54") (pin "1") (pinfunction "1_1") (pintype "passive"))
      (node (ref "R53") (pin "1") (pinfunction "1_1") (pintype "passive"))
      (node (ref "U51") (pin "1") (pinfunction "MPP-SET_1") (pintype "input"))
      (node (ref "U51") (pin "8") (pinfunction "Xshut_8") (pintype "input"))
    )
    (net (code "66") (name "Net-(U51-Vctrl)") (class "Default")
      (node (ref "C52") (pin "1") (pinfunction "1_1") (pintype "passive"))
      (node (ref "R51") (pin "1") (pinfunction "1_1") (pintype "passive"))
      (node (ref "R52") (pin "2") (pinfunction "2_2") (pintype "passive"))
      (node (ref "U51") (pin "5") (pinfunction "Vctrl_5") (pintype "input"))
    )
    (net (code "67") (name "Net-(U51-Vout)") (class "Default")
      (node (ref "Cout5") (pin "2") (pinfunction "2_2") (pintype "passive"))
      (node (ref "Dout5") (pin "1") (pinfunction "1_1") (pintype "passive"))
      (node (ref "Rf51") (pin "1") (pinfunction "1_1") (pintype "passive"))
      (node (ref "Rs5") (pin "1") (pinfunction "1_1") (pintype "passive"))
      (node (ref "U51") (pin "4") (pinfunction "Vout_4") (pintype "output"))
    )
    (net (code "68") (name "Net-(U52-Iend)") (class "Default")
      (node (ref "R56") (pin "1") (pinfunction "1_1") (pintype "passive"))
      (node (ref "U52") (pin "13") (pinfunction "Iend_13") (pintype "bidirectional"))
    )
    (net (code "69") (name "Net-(U52-Ipre)") (class "Default")
      (node (ref "R54") (pin "1") (pinfunction "1_1") (pintype "passive"))
      (node (ref "U52") (pin "16") (pinfunction "Ipre_16") (pintype "input"))
    )
    (net (code "70") (name "Net-(U52-Iprg)") (class "Default")
      (node (ref "R55") (pin "1") (pinfunction "1_1") (pintype "passive"))
      (node (ref "U52") (pin "15") (pinfunction "Iprg_15") (pintype "input"))
    )
    (net (code "71") (name "Net-(U52-Tprg)") (class "Default")
      (node (ref "C56") (pin "2") (pinfunction "2_2") (pintype "passive"))
      (node (ref "U52") (pin "5") (pinfunction "Tprg_5") (pintype "input"))
    )
    (net (code "72") (name "Net-(U52-Vin)") (class "Default")
      (node (ref "C55") (pin "1") (pinfunction "1_1") (pintype "passive"))
      (node (ref "R51") (pin "2") (pinfunction "2_2") (pintype "passive"))
      (node (ref "Rf52") (pin "1") (pinfunction "1_1") (pintype "passive"))
      (node (ref "Rs5") (pin "2") (pinfunction "2_2") (pintype "passive"))
      (node (ref "U52") (pin "1") (pinfunction "Vin_1") (pintype "power_in"))
      (node (ref "U52") (pin "2") (pinfunction "Vinsns_2") (pintype "input"))
    )
    (net (code "73") (name "Net-(U52-Vref)") (class "Default")
      (node (ref "C58") (pin "1") (pinfunction "1_1") (pintype "passive"))
      (node (ref "U52") (pin "12") (pinfunction "Vref_12") (pintype "output"))
    )
    (net (code "74") (name "unconnected-(U12-TH-Pad8)") (class "Default")
      (node (ref "U12") (pin "8") (pinfunction "TH_8") (pintype "input+no_connect"))
    )
    (net (code "75") (name "unconnected-(U12-Vpre-Pad14)") (class "Default")
      (node (ref "U12") (pin "14") (pinfunction "Vpre_14") (pintype "input+no_connect"))
    )
    (net (code "76") (name "unconnected-(U22-TH-Pad8)") (class "Default")
      (node (ref "U22") (pin "8") (pinfunction "TH_8") (pintype "input+no_connect"))
    )
    (net (code "77") (name "unconnected-(U22-Vpre-Pad14)") (class "Default")
      (node (ref "U22") (pin "14") (pinfunction "Vpre_14") (pintype "input+no_connect"))
    )
    (net (code "78") (name "unconnected-(U32-TH-Pad8)") (class "Default")
      (node (ref "U32") (pin "8") (pinfunction "TH_8") (pintype "input+no_connect"))
    )
    (net (code "79") (name "unconnected-(U32-Vpre-Pad14)") (class "Default")
      (node (ref "U32") (pin "14") (pinfunction "Vpre_14") (pintype "input+no_connect"))
    )
    (net (code "80") (name "unconnected-(U42-ST1-Pad4)") (class "Default")
      (node (ref "U42") (pin "4") (pinfunction "ST1_4") (pintype "open_collector"))
    )
    (net (code "81") (name "unconnected-(U42-ST2-Pad3)") (class "Default")
      (node (ref "U42") (pin "3") (pinfunction "ST2_3") (pintype "open_collector"))
    )
    (net (code "82") (name "unconnected-(U42-TH-Pad8)") (class "Default")
      (node (ref "U42") (pin "8") (pinfunction "TH_8") (pintype "input+no_connect"))
    )
    (net (code "83") (name "unconnected-(U42-Vpre-Pad14)") (class "Default")
      (node (ref "U42") (pin "14") (pinfunction "Vpre_14") (pintype "input+no_connect"))
    )
    (net (code "84") (name "unconnected-(U52-ST1-Pad4)") (class "Default")
      (node (ref "U52") (pin "4") (pinfunction "ST1_4") (pintype "open_collector"))
    )
    (net (code "85") (name "unconnected-(U52-ST2-Pad3)") (class "Default")
      (node (ref "U52") (pin "3") (pinfunction "ST2_3") (pintype "open_collector"))
    )
    (net (code "86") (name "unconnected-(U52-TH-Pad8)") (class "Default")
      (node (ref "U52") (pin "8") (pinfunction "TH_8") (pintype "input+no_connect"))
    )
    (net (code "87") (name "unconnected-(U52-Vpre-Pad14)") (class "Default")
      (node (ref "U52") (pin "14") (pinfunction "Vpre_14") (pintype "input+no_connect"))
    )
  )
)
